# HFM_Power_Supply_V1.net
KiCad netlist of a schematic drawn in Altium Designer
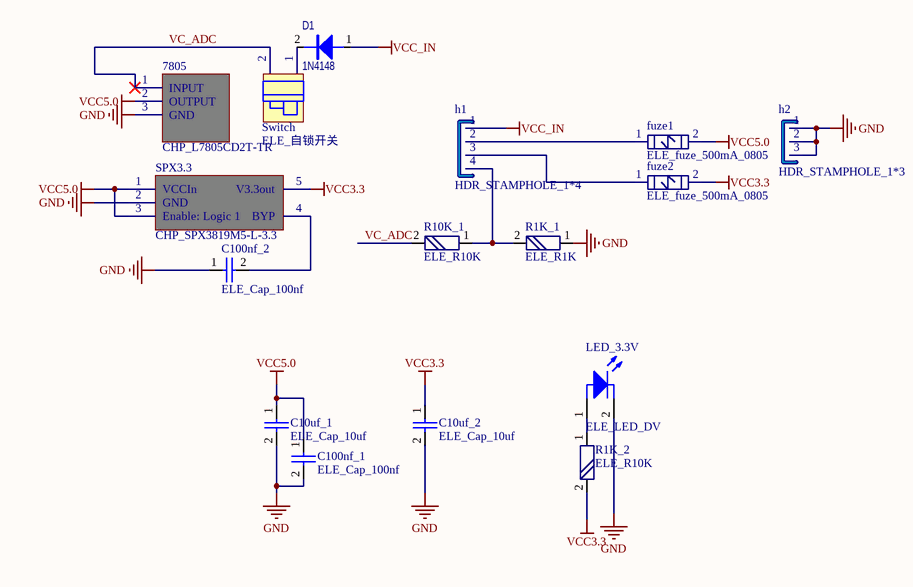
[diagram p0: HFM_Power_Supply_V1.SchDoc]

(export (version "E")
  (design (tool "Eeschema 10.0.6"))
  (components
    (comp (ref "7805")
      (value "CHP_L7805CD2T-TR")
      (footprint "CHP_TOD2PAK")
      (description "5.0稳压器")
      (libsource (lib "Hands_free") (part "CHP_L7805CD2T-TR"))
    )
    (comp (ref "C10uf_1")
      (value "ELE_Cap_10uf")
      (footprint "ELE_0603_P")
      (description "电容10uf固定")
      (libsource (lib "Hands_free") (part "ELE_Cap_10uf"))
    )
    (comp (ref "C10uf_2")
      (value "ELE_Cap_10uf")
      (footprint "ELE_0603_P")
      (description "电容10uf固定")
      (libsource (lib "Hands_free") (part "ELE_Cap_10uf"))
    )
    (comp (ref "C100nf_1")
      (value "ELE_Cap_100nf")
      (footprint "ELE_0603_P")
      (description "电容100nf固定")
      (libsource (lib "Hands_free") (part "ELE_Cap_100nf"))
    )
    (comp (ref "C100nf_2")
      (value "ELE_Cap_100nf")
      (footprint "ELE_0603_P")
      (description "电容100nf固定")
      (libsource (lib "Hands_free") (part "ELE_Cap_100nf"))
    )
    (comp (ref "D1")
      (value "1N4148")
      (footprint "ELE_D1206")
      (description "二极管")
      (libsource (lib "Hands_free") (part "ELE_Diode"))
    )
    (comp (ref "fuze1")
      (value "ELE_fuze_500mA_0805")
      (footprint "ELE_FUZE_0805")
      (libsource (lib "Hands_free") (part "ELE_fuze_500mA_0805"))
    )
    (comp (ref "fuze2")
      (value "ELE_fuze_500mA_0805")
      (footprint "ELE_FUZE_0805")
      (libsource (lib "Hands_free") (part "ELE_fuze_500mA_0805"))
    )
    (comp (ref "h1")
      (value "HDR_STAMPHOLE_1*4")
      (footprint "HDR_STAMPHOLE_2.00_DH_1*4")
      (libsource (lib "Hands_free") (part "HDR_STAMPHOLE_1*4"))
    )
    (comp (ref "h2")
      (value "HDR_STAMPHOLE_1*3")
      (footprint "HDR_STAMPHOLE_2.00_DH_1*3")
      (libsource (lib "Hands_free") (part "HDR_STAMPHOLE_1*3"))
    )
    (comp (ref "LED_3.3V")
      (value "ELE_LED_DV")
      (footprint "ELE_LED_DV")
      (description "发光二极管 直插")
      (fields (field (name "PUBLISHER") "Altium Limited"))
      (libsource (lib "Hands_free") (part "ELE_LED_DV"))
    )
    (comp (ref "R1K_1")
      (value "ELE_R1K")
      (footprint "ELE_0603_P")
      (description "电阻1K固定")
      (libsource (lib "Hands_free") (part "ELE_R1K"))
    )
    (comp (ref "R1K_2")
      (value "ELE_R10K")
      (footprint "ELE_0603_P")
      (description "电阻10K固定")
      (libsource (lib "Hands_free") (part "ELE_R10K"))
    )
    (comp (ref "R10K_1")
      (value "ELE_R10K")
      (footprint "ELE_0603_P")
      (description "电阻10K固定")
      (libsource (lib "Hands_free") (part "ELE_R10K"))
    )
    (comp (ref "SPX3.3")
      (value "CHP_SPX3819M5-L-3.3")
      (footprint "CHP_SOT23_P_5P")
      (description "3.3V稳压")
      (libsource (lib "Hands_free") (part "CHP_SPX3819M5-L-3.3"))
    )
    (comp (ref "Switch")
      (value "ELE_自锁开关")
      (footprint "ELE_自锁开关_DV_5.8*5.8")
      (libsource (lib "Hands_free") (part "ELE_自锁开关"))
    )
  )
  (nets
    (net (code "1") (name "/VC_ADC") (class "Default")
      (node (ref "7805") (pin "1") (pinfunction "INPUT_1") (pintype "passive"))
      (node (ref "R10K_1") (pin "2") (pintype "passive"))
      (node (ref "Switch") (pin "2") (pintype "passive"))
    )
    (net (code "2") (name "GND") (class "Default")
      (node (ref "7805") (pin "3") (pinfunction "GND_3") (pintype "passive"))
      (node (ref "C100nf_1") (pin "2") (pintype "passive"))
      (node (ref "C100nf_2") (pin "1") (pintype "passive"))
      (node (ref "C10uf_1") (pin "2") (pintype "passive"))
      (node (ref "C10uf_2") (pin "2") (pintype "passive"))
      (node (ref "LED_3.3V") (pin "2") (pintype "passive"))
      (node (ref "R1K_1") (pin "1") (pintype "passive"))
      (node (ref "SPX3.3") (pin "2") (pinfunction "GND_2") (pintype "passive"))
      (node (ref "h2") (pin "1") (pintype "passive"))
      (node (ref "h2") (pin "2") (pintype "passive"))
      (node (ref "h2") (pin "3") (pintype "passive"))
    )
    (net (code "3") (name "Net-(D1-Pad2)") (class "Default")
      (node (ref "D1") (pin "2") (pintype "passive"))
      (node (ref "Switch") (pin "1") (pintype "passive"))
    )
    (net (code "4") (name "Net-(LED_3.3V-Pad1)") (class "Default")
      (node (ref "LED_3.3V") (pin "1") (pintype "passive"))
      (node (ref "R1K_2") (pin "1") (pintype "passive"))
    )
    (net (code "5") (name "Net-(R10K_1-Pad1)") (class "Default")
      (node (ref "R10K_1") (pin "1") (pintype "passive"))
      (node (ref "R1K_1") (pin "2") (pintype "passive"))
      (node (ref "h1") (pin "4") (pintype "passive"))
    )
    (net (code "6") (name "Net-(SPX3.3-BYP)") (class "Default")
      (node (ref "C100nf_2") (pin "2") (pintype "passive"))
      (node (ref "SPX3.3") (pin "4") (pinfunction "BYP_4") (pintype "passive"))
    )
    (net (code "7") (name "Net-(fuze1-Pad1)") (class "Default")
      (node (ref "fuze1") (pin "1") (pintype "passive"))
      (node (ref "h1") (pin "2") (pintype "passive"))
    )
    (net (code "8") (name "Net-(fuze2-Pad1)") (class "Default")
      (node (ref "fuze2") (pin "1") (pintype "passive"))
      (node (ref "h1") (pin "3") (pintype "passive"))
    )
    (net (code "9") (name "VCC3.3") (class "Default")
      (node (ref "C10uf_2") (pin "1") (pintype "passive"))
      (node (ref "R1K_2") (pin "2") (pintype "passive"))
      (node (ref "SPX3.3") (pin "5") (pinfunction "V3.3out_5") (pintype "passive"))
      (node (ref "fuze2") (pin "2") (pintype "passive"))
    )
    (net (code "10") (name "VCC5.0") (class "Default")
      (node (ref "7805") (pin "2") (pinfunction "OUTPUT_2") (pintype "passive"))
      (node (ref "C100nf_1") (pin "1") (pintype "passive"))
      (node (ref "C10uf_1") (pin "1") (pintype "passive"))
      (node (ref "SPX3.3") (pin "1") (pinfunction "VCCIn_1") (pintype "passive"))
      (node (ref "SPX3.3") (pin "3") (pinfunction "Enable:_Logic_1_3") (pintype "passive"))
      (node (ref "fuze1") (pin "2") (pintype "passive"))
    )
    (net (code "11") (name "VCC_IN") (class "Default")
      (node (ref "D1") (pin "1") (pintype "passive"))
      (node (ref "h1") (pin "1") (pintype "passive"))
    )
  )
)
